# TrackerBase2.net
KiCad netlist of a schematic drawn in EAGLE
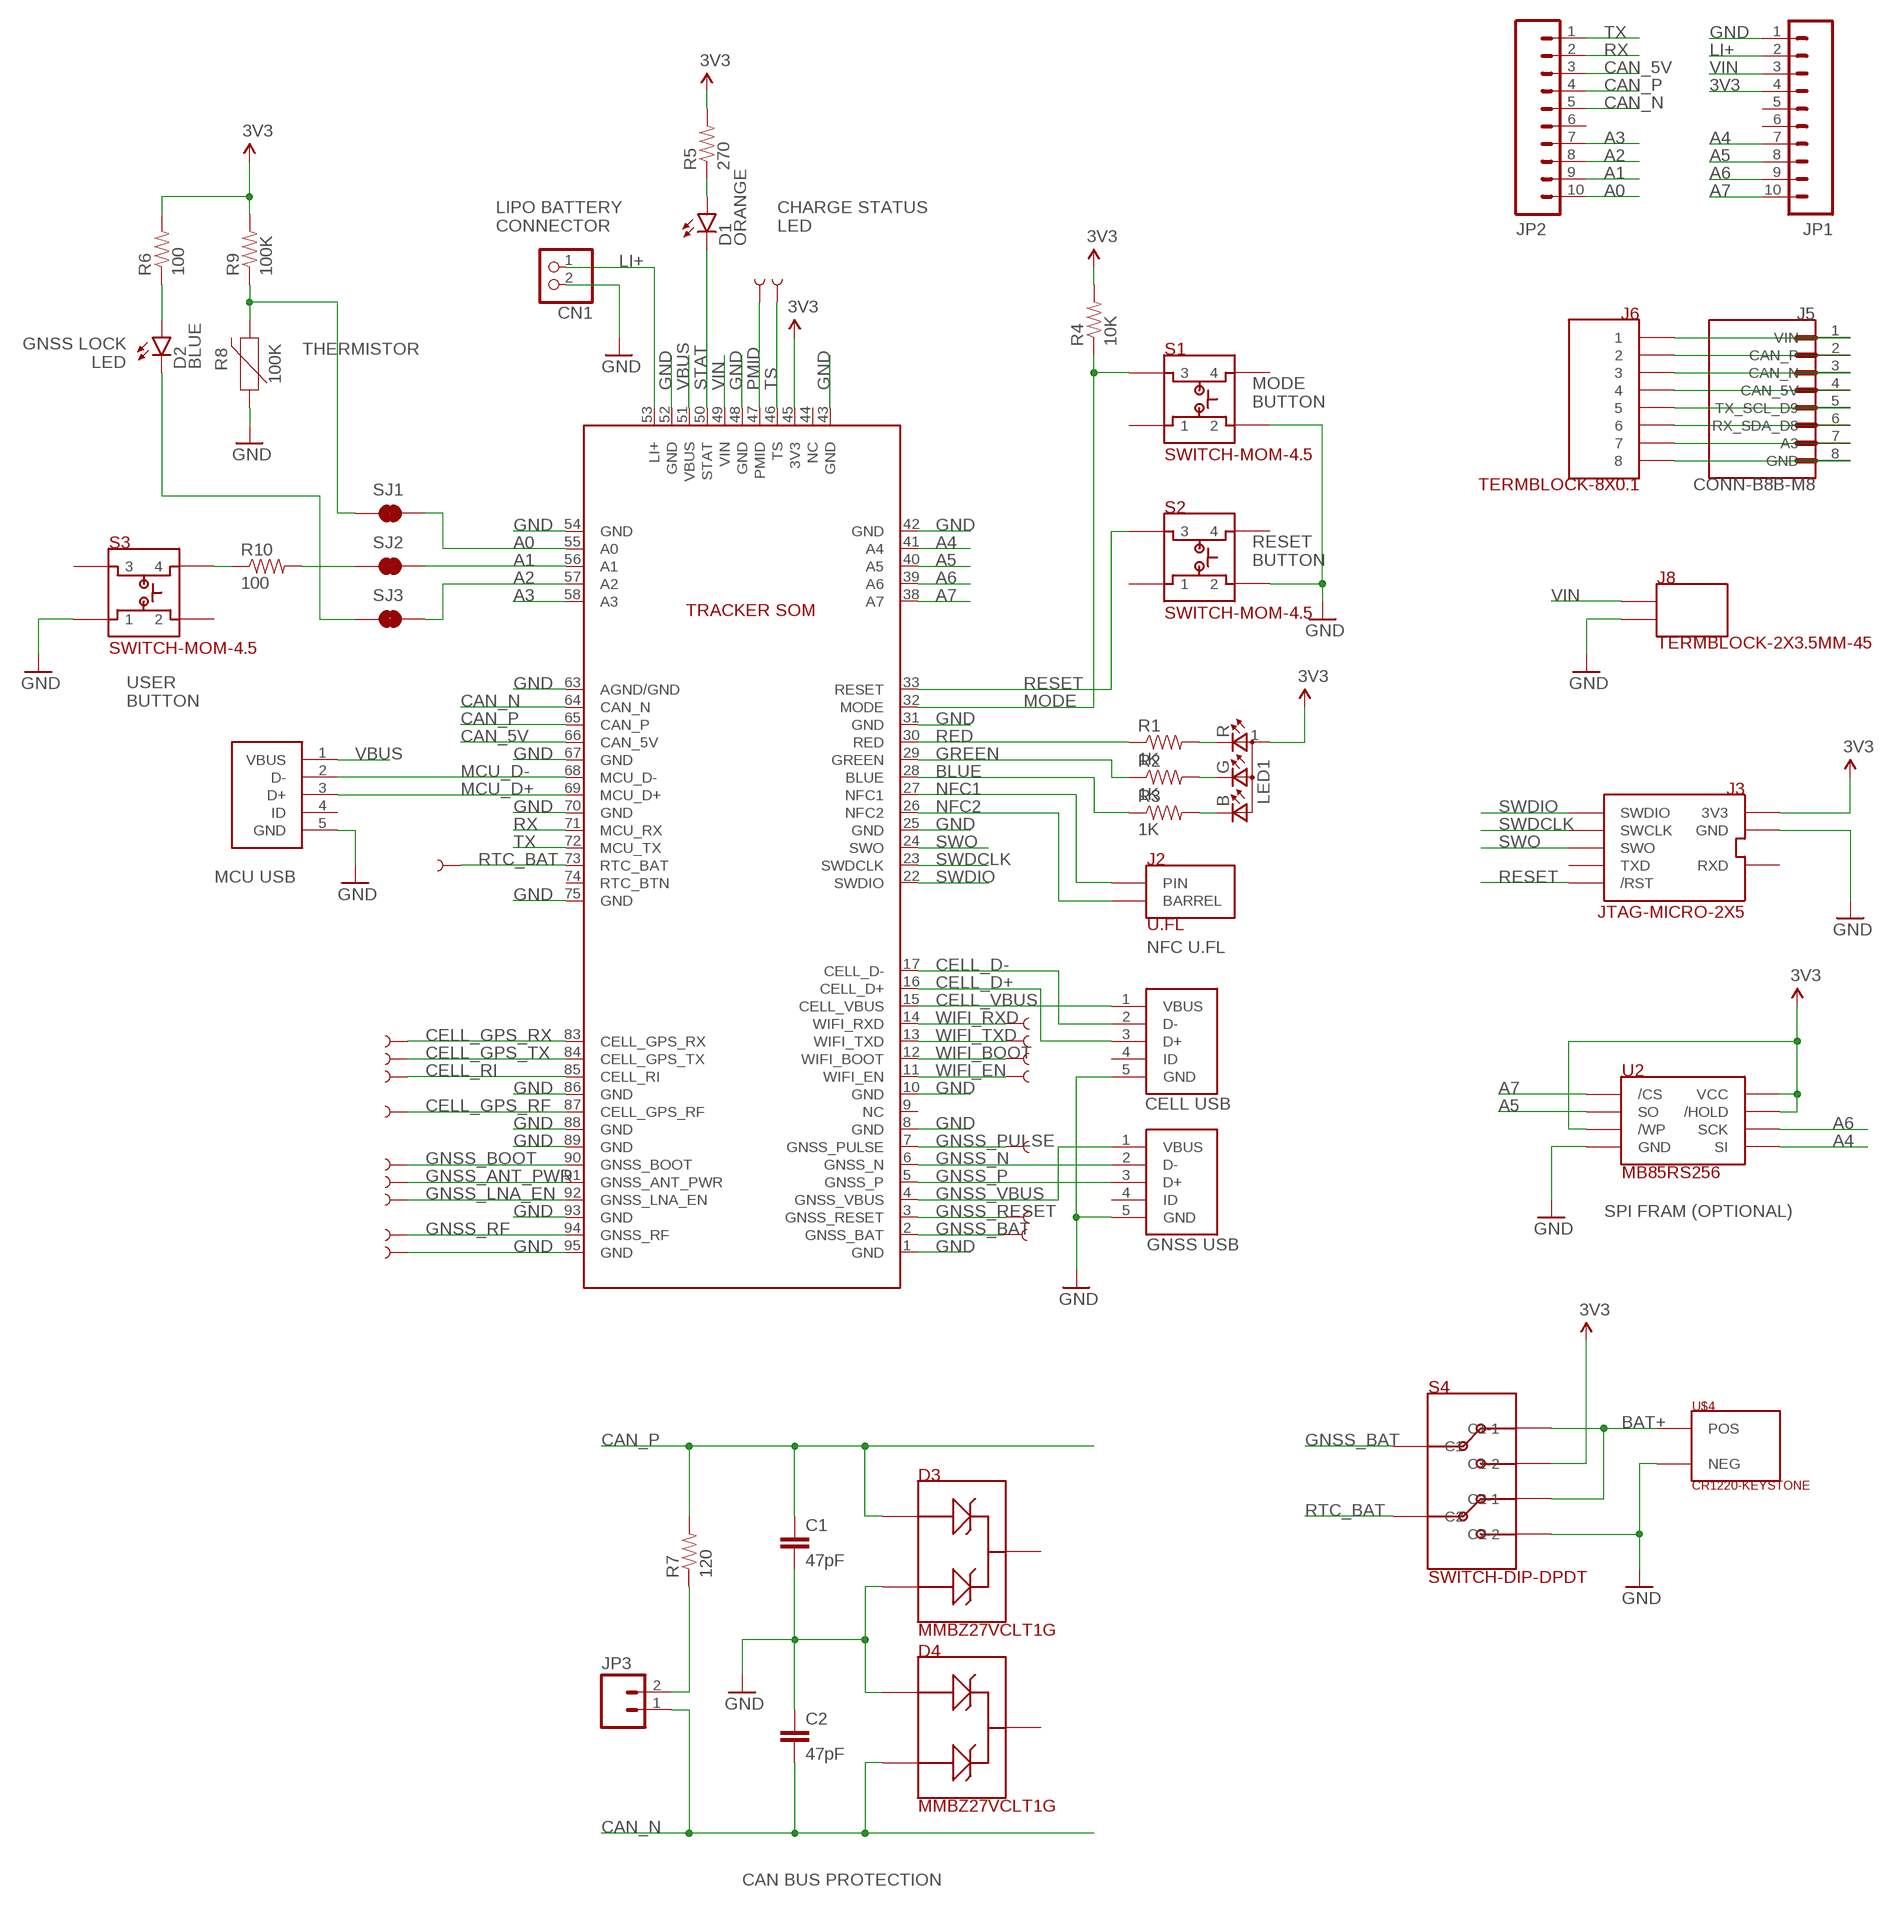
[diagram p0: schematic, sheet 1]

(export (version "E")
  (design (tool "Eeschema 10.0.6"))
  (components
    (comp (ref "C1")
      (value "47pF")
      (footprint "eagle-import:0603-CAP")
      (libsource (lib "eagle-import") (part "CAP-47PF-0603"))
    )
    (comp (ref "C2")
      (value "47pF")
      (footprint "eagle-import:0603-CAP")
      (libsource (lib "eagle-import") (part "CAP-47PF-0603"))
    )
    (comp (ref "CN1")
      (value "JST_2PIN-THM")
      (footprint "eagle-import:JST-PH-2-THM")
      (libsource (lib "eagle-import") (part "JST_2PIN-THM"))
    )
    (comp (ref "D1")
      (value "ORANGE")
      (footprint "eagle-import:LED-0603")
      (libsource (lib "eagle-import") (part "LED-ORANGE0603"))
    )
    (comp (ref "D2")
      (value "BLUE")
      (footprint "eagle-import:LED-0603")
      (libsource (lib "eagle-import") (part "LED-BLUE0603"))
    )
    (comp (ref "D3")
      (value "MMBZ27VCLT1G")
      (footprint "eagle-import:SOT-23-3-ON")
      (libsource (lib "eagle-import") (part "TVS-MMBZ27VCLT1G"))
    )
    (comp (ref "D4")
      (value "MMBZ27VCLT1G")
      (footprint "eagle-import:SOT-23-3-ON")
      (libsource (lib "eagle-import") (part "TVS-MMBZ27VCLT1G"))
    )
    (comp (ref "J1")
      (value "USB-MICRO-B-VERT-PTH")
      (footprint "eagle-import:USB-MICRO-B-VERT-PTH")
      (libsource (lib "eagle-import") (part "USB-MICRO-B-VERT-PTH"))
    )
    (comp (ref "J2")
      (value "U.FL")
      (footprint "eagle-import:CONN-UFL-TE")
      (libsource (lib "eagle-import") (part "CONN-UFL-TE"))
    )
    (comp (ref "J3")
      (value "JTAG-MICRO-2X5")
      (footprint "eagle-import:JTAG-MICRO-2X5")
      (libsource (lib "eagle-import") (part "JTAG-MICRO-2X5"))
    )
    (comp (ref "J4")
      (value "USB-MICRO-B-VERT-PTH")
      (footprint "eagle-import:USB-MICRO-B-VERT-PTH")
      (libsource (lib "eagle-import") (part "USB-MICRO-B-VERT-PTH"))
    )
    (comp (ref "J5")
      (value "CONN-B8B-M8")
      (footprint "eagle-import:JST_B8B-PH-SM4-TB(LF)(SN)")
      (libsource (lib "eagle-import") (part "CONN-B8B-M8"))
    )
    (comp (ref "J6")
      (value "TERMBLOCK-8X0.1")
      (footprint "eagle-import:TERMBLOCK-8X0.1")
      (libsource (lib "eagle-import") (part "TERMBLOCK-8X0.1"))
    )
    (comp (ref "J7")
      (value "USB-MICRO-B-VERT-PTH")
      (footprint "eagle-import:USB-MICRO-B-VERT-PTH")
      (libsource (lib "eagle-import") (part "USB-MICRO-B-VERT-PTH"))
    )
    (comp (ref "J8")
      (value "TERMBLOCK-2X3.5MM-45")
      (footprint "eagle-import:TERMBLOCK-2X3.5MM-45")
      (libsource (lib "eagle-import") (part "TERMBLOCK-2X3.5MM-45"))
    )
    (comp (ref "JP1")
      (value "M10")
      (footprint "eagle-import:1X10")
      (libsource (lib "eagle-import") (part "M10"))
    )
    (comp (ref "JP2")
      (value "M10")
      (footprint "eagle-import:1X10")
      (libsource (lib "eagle-import") (part "M10"))
    )
    (comp (ref "JP3")
      (value "M02PTH")
      (footprint "eagle-import:1X02")
      (libsource (lib "eagle-import") (part "M02PTH"))
    )
    (comp (ref "LED1")
      (value "RGB")
      (footprint "eagle-import:LED-RGB-CREE-SMD")
      (libsource (lib "eagle-import") (part "LED-RGB-CREE-SMD"))
    )
    (comp (ref "R1")
      (value "1K")
      (footprint "eagle-import:0603-RES")
      (libsource (lib "eagle-import") (part "RES-1K-0603"))
    )
    (comp (ref "R2")
      (value "1K")
      (footprint "eagle-import:0603-RES")
      (libsource (lib "eagle-import") (part "RES-1K-0603"))
    )
    (comp (ref "R3")
      (value "1K")
      (footprint "eagle-import:0603-RES")
      (libsource (lib "eagle-import") (part "RES-1K-0603"))
    )
    (comp (ref "R4")
      (value "10K")
      (footprint "eagle-import:0603-RES")
      (libsource (lib "eagle-import") (part "RES-10K-06030603"))
    )
    (comp (ref "R5")
      (value "270")
      (footprint "eagle-import:0603-RES")
      (libsource (lib "eagle-import") (part "RES-270-0603.DEV"))
    )
    (comp (ref "R6")
      (value "100")
      (footprint "eagle-import:0603-RES")
      (libsource (lib "eagle-import") (part "RES-100-0603.DEV"))
    )
    (comp (ref "R7")
      (value "120")
      (footprint "eagle-import:0603-RES")
      (libsource (lib "eagle-import") (part "RES-120-0603"))
    )
    (comp (ref "R8")
      (value "100K")
      (footprint "eagle-import:0603")
      (libsource (lib "eagle-import") (part "NTC-THERMISTOR-0603"))
    )
    (comp (ref "R9")
      (value "100K")
      (footprint "eagle-import:0603-RES")
      (libsource (lib "eagle-import") (part "RES-100K-0603"))
    )
    (comp (ref "R10")
      (value "100")
      (footprint "eagle-import:0603-RES")
      (libsource (lib "eagle-import") (part "RES-100-0603.DEV"))
    )
    (comp (ref "S1")
      (value "SWITCH-MOM-4.5")
      (footprint "eagle-import:SWITCH-MOM-4.5")
      (libsource (lib "eagle-import") (part "SWITCH-MOM-4.5"))
    )
    (comp (ref "S2")
      (value "SWITCH-MOM-4.5")
      (footprint "eagle-import:SWITCH-MOM-4.5")
      (libsource (lib "eagle-import") (part "SWITCH-MOM-4.5"))
    )
    (comp (ref "S3")
      (value "SWITCH-MOM-4.5")
      (footprint "eagle-import:SWITCH-MOM-4.5")
      (libsource (lib "eagle-import") (part "SWITCH-MOM-4.5"))
    )
    (comp (ref "S4")
      (value "SWITCH-DIP-DPDT")
      (footprint "eagle-import:SWITCH-DIP-DPDT")
      (libsource (lib "eagle-import") (part "SWITCH-DIP-DPDT"))
    )
    (comp (ref "SJ1")
      (value "JUMPER-PAD-2-NC_BY_TRACENO_SILK")
      (footprint "eagle-import:PAD-JUMPER-2-NC_BY_TRACE_NO_SILK")
      (libsource (lib "eagle-import") (part "JUMPER-PAD-2-NC_BY_TRACENO_SILK"))
    )
    (comp (ref "SJ2")
      (value "JUMPER-PAD-2-NC_BY_TRACENO_SILK")
      (footprint "eagle-import:PAD-JUMPER-2-NC_BY_TRACE_NO_SILK")
      (libsource (lib "eagle-import") (part "JUMPER-PAD-2-NC_BY_TRACENO_SILK"))
    )
    (comp (ref "SJ3")
      (value "JUMPER-PAD-2-NC_BY_TRACENO_SILK")
      (footprint "eagle-import:PAD-JUMPER-2-NC_BY_TRACE_NO_SILK")
      (libsource (lib "eagle-import") (part "JUMPER-PAD-2-NC_BY_TRACENO_SILK"))
    )
    (comp (ref "TP1")
      (value "TEST-POINTTP_15TH_THRU")
      (footprint "eagle-import:TP_15TH")
      (libsource (lib "eagle-import") (part "TEST-POINTTP_15TH_THRU"))
    )
    (comp (ref "TP2")
      (value "TEST-POINTTP_15TH_THRU")
      (footprint "eagle-import:TP_15TH")
      (libsource (lib "eagle-import") (part "TEST-POINTTP_15TH_THRU"))
    )
    (comp (ref "TP3")
      (value "TEST-POINTTP_15TH_THRU")
      (footprint "eagle-import:TP_15TH")
      (libsource (lib "eagle-import") (part "TEST-POINTTP_15TH_THRU"))
    )
    (comp (ref "TP4")
      (value "TEST-POINTTP_15TH_THRU")
      (footprint "eagle-import:TP_15TH")
      (libsource (lib "eagle-import") (part "TEST-POINTTP_15TH_THRU"))
    )
    (comp (ref "TP5")
      (value "TEST-POINTTP_15TH_THRU")
      (footprint "eagle-import:TP_15TH")
      (libsource (lib "eagle-import") (part "TEST-POINTTP_15TH_THRU"))
    )
    (comp (ref "TP6")
      (value "TEST-POINTTP_15TH_THRU")
      (footprint "eagle-import:TP_15TH")
      (libsource (lib "eagle-import") (part "TEST-POINTTP_15TH_THRU"))
    )
    (comp (ref "TP7")
      (value "TEST-POINTTP_15TH_THRU")
      (footprint "eagle-import:TP_15TH")
      (libsource (lib "eagle-import") (part "TEST-POINTTP_15TH_THRU"))
    )
    (comp (ref "TP8")
      (value "TEST-POINTTP_15TH_THRU")
      (footprint "eagle-import:TP_15TH")
      (libsource (lib "eagle-import") (part "TEST-POINTTP_15TH_THRU"))
    )
    (comp (ref "TP9")
      (value "TEST-POINTTP_15TH_THRU")
      (footprint "eagle-import:TP_15TH")
      (libsource (lib "eagle-import") (part "TEST-POINTTP_15TH_THRU"))
    )
    (comp (ref "TP10")
      (value "TEST-POINTTP_15TH_THRU")
      (footprint "eagle-import:TP_15TH")
      (libsource (lib "eagle-import") (part "TEST-POINTTP_15TH_THRU"))
    )
    (comp (ref "TP11")
      (value "TEST-POINTTP_15TH_THRU")
      (footprint "eagle-import:TP_15TH")
      (libsource (lib "eagle-import") (part "TEST-POINTTP_15TH_THRU"))
    )
    (comp (ref "TP12")
      (value "TEST-POINTTP_15TH_THRU")
      (footprint "eagle-import:TP_15TH")
      (libsource (lib "eagle-import") (part "TEST-POINTTP_15TH_THRU"))
    )
    (comp (ref "TP13")
      (value "TEST-POINTTP_15TH_THRU")
      (footprint "eagle-import:TP_15TH")
      (libsource (lib "eagle-import") (part "TEST-POINTTP_15TH_THRU"))
    )
    (comp (ref "TP14")
      (value "TEST-POINTTP_15TH_THRU")
      (footprint "eagle-import:TP_15TH")
      (libsource (lib "eagle-import") (part "TEST-POINTTP_15TH_THRU"))
    )
    (comp (ref "TP15")
      (value "TEST-POINTTP_15TH_THRU")
      (footprint "eagle-import:TP_15TH")
      (libsource (lib "eagle-import") (part "TEST-POINTTP_15TH_THRU"))
    )
    (comp (ref "TP16")
      (value "TEST-POINTTP_15TH_THRU")
      (footprint "eagle-import:TP_15TH")
      (libsource (lib "eagle-import") (part "TEST-POINTTP_15TH_THRU"))
    )
    (comp (ref "TP17")
      (value "TEST-POINTTP_15TH_THRU")
      (footprint "eagle-import:TP_15TH")
      (libsource (lib "eagle-import") (part "TEST-POINTTP_15TH_THRU"))
    )
    (comp (ref "TP18")
      (value "TEST-POINTTP_15TH_THRU")
      (footprint "eagle-import:TP_15TH")
      (libsource (lib "eagle-import") (part "TEST-POINTTP_15TH_THRU"))
    )
    (comp (ref "TP19")
      (value "TEST-POINTTP_15TH_THRU")
      (footprint "eagle-import:TP_15TH")
      (libsource (lib "eagle-import") (part "TEST-POINTTP_15TH_THRU"))
    )
    (comp (ref "U$4")
      (value "CR1220-KEYSTONE")
      (footprint "eagle-import:CR1220-KEYSTONE")
      (libsource (lib "eagle-import") (part "CR1220-KEYSTONE"))
    )
    (comp (ref "U1")
      (value "TRACKER-SOM-SKIP-NC")
      (footprint "eagle-import:TRACKER-SOM-SKIP-NC")
      (libsource (lib "eagle-import") (part "TRACKER-SOM-SKIP-NC"))
    )
    (comp (ref "U2")
      (value "MB85RS256")
      (footprint "eagle-import:8-SOIC-MAXIM")
      (libsource (lib "eagle-import") (part "MB85RS256-FRAM"))
    )
  )
  (nets
    (net (code "1") (name "/A0") (class "Default")
      (node (ref "JP2") (pin "10") (pinfunction "10_10") (pintype "passive"))
      (node (ref "SJ1") (pin "2") (pinfunction "2_2") (pintype "passive"))
      (node (ref "U1") (pin "55") (pinfunction "A0_55") (pintype "bidirectional"))
    )
    (net (code "2") (name "/A1") (class "Default")
      (node (ref "JP2") (pin "9") (pinfunction "9_9") (pintype "passive"))
      (node (ref "SJ2") (pin "2") (pinfunction "2_2") (pintype "passive"))
      (node (ref "U1") (pin "56") (pinfunction "A1_56") (pintype "bidirectional"))
    )
    (net (code "3") (name "/A2") (class "Default")
      (node (ref "JP2") (pin "8") (pinfunction "8_8") (pintype "passive"))
      (node (ref "SJ3") (pin "2") (pinfunction "2_2") (pintype "passive"))
      (node (ref "U1") (pin "57") (pinfunction "A2_57") (pintype "bidirectional"))
    )
    (net (code "4") (name "/A3") (class "Default")
      (node (ref "J5") (pin "7") (pinfunction "A3_7") (pintype "passive"))
      (node (ref "J6") (pin "P$7") (pinfunction "7_P$7") (pintype "passive"))
      (node (ref "JP2") (pin "7") (pinfunction "7_7") (pintype "passive"))
      (node (ref "U1") (pin "58") (pinfunction "A3_58") (pintype "bidirectional"))
    )
    (net (code "5") (name "/A4") (class "Default")
      (node (ref "JP1") (pin "7") (pinfunction "7_7") (pintype "passive"))
      (node (ref "U1") (pin "41") (pinfunction "A4_41") (pintype "bidirectional"))
      (node (ref "U2") (pin "5") (pinfunction "SI_5") (pintype "input"))
    )
    (net (code "6") (name "/A5") (class "Default")
      (node (ref "JP1") (pin "8") (pinfunction "8_8") (pintype "passive"))
      (node (ref "U1") (pin "40") (pinfunction "A5_40") (pintype "bidirectional"))
      (node (ref "U2") (pin "2") (pinfunction "SO_2") (pintype "output"))
    )
    (net (code "7") (name "/A6") (class "Default")
      (node (ref "JP1") (pin "9") (pinfunction "9_9") (pintype "passive"))
      (node (ref "U1") (pin "39") (pinfunction "A6_39") (pintype "bidirectional"))
      (node (ref "U2") (pin "6") (pinfunction "SCK_6") (pintype "input"))
    )
    (net (code "8") (name "/A7") (class "Default")
      (node (ref "JP1") (pin "10") (pinfunction "10_10") (pintype "passive"))
      (node (ref "U1") (pin "38") (pinfunction "A7_38") (pintype "bidirectional"))
      (node (ref "U2") (pin "1") (pinfunction "/CS_1") (pintype "input"))
    )
    (net (code "9") (name "/BAT+") (class "Default")
      (node (ref "S4") (pin "C1-1") (pinfunction "C1-1_C1-1") (pintype "passive"))
      (node (ref "S4") (pin "C2-1") (pinfunction "C2-1_C2-1") (pintype "passive"))
      (node (ref "U$4") (pin "POS") (pinfunction "POS_POS") (pintype "passive"))
    )
    (net (code "10") (name "/BLUE") (class "Default")
      (node (ref "R3") (pin "1") (pinfunction "1_1") (pintype "passive"))
      (node (ref "U1") (pin "28") (pinfunction "BLUE_28") (pintype "bidirectional"))
    )
    (net (code "11") (name "/CAN_5V") (class "Default")
      (node (ref "J5") (pin "4") (pinfunction "CAN_5V_4") (pintype "passive"))
      (node (ref "J6") (pin "P$4") (pinfunction "4_P$4") (pintype "passive"))
      (node (ref "JP2") (pin "3") (pinfunction "3_3") (pintype "passive"))
      (node (ref "U1") (pin "66") (pinfunction "CAN_5V_66") (pintype "bidirectional"))
    )
    (net (code "12") (name "/CAN_N") (class "Default")
      (node (ref "C2") (pin "2") (pinfunction "2_2") (pintype "passive"))
      (node (ref "D4") (pin "2") (pinfunction "2_2") (pintype "bidirectional"))
      (node (ref "J5") (pin "3") (pinfunction "CAN_N_3") (pintype "passive"))
      (node (ref "J6") (pin "P$3") (pinfunction "3_P$3") (pintype "passive"))
      (node (ref "JP2") (pin "5") (pinfunction "5_5") (pintype "passive"))
      (node (ref "JP3") (pin "1") (pinfunction "1_1") (pintype "passive"))
      (node (ref "U1") (pin "64") (pinfunction "CAN_N_64") (pintype "bidirectional"))
    )
    (net (code "13") (name "/CAN_P") (class "Default")
      (node (ref "C1") (pin "1") (pinfunction "1_1") (pintype "passive"))
      (node (ref "D3") (pin "1") (pinfunction "1_1") (pintype "bidirectional"))
      (node (ref "J5") (pin "2") (pinfunction "CAN_P_2") (pintype "passive"))
      (node (ref "J6") (pin "P$2") (pinfunction "2_P$2") (pintype "passive"))
      (node (ref "JP2") (pin "4") (pinfunction "4_4") (pintype "passive"))
      (node (ref "R7") (pin "2") (pinfunction "2_2") (pintype "passive"))
      (node (ref "U1") (pin "65") (pinfunction "CAN_P_65") (pintype "bidirectional"))
    )
    (net (code "14") (name "/CELL_D+") (class "Default")
      (node (ref "J1") (pin "3") (pinfunction "D+_3") (pintype "passive"))
      (node (ref "U1") (pin "16") (pinfunction "CELL_D+_16") (pintype "bidirectional"))
    )
    (net (code "15") (name "/CELL_D-") (class "Default")
      (node (ref "J1") (pin "2") (pinfunction "D-_2") (pintype "passive"))
      (node (ref "U1") (pin "17") (pinfunction "CELL_D-_17") (pintype "bidirectional"))
    )
    (net (code "16") (name "/CELL_GPS_RF") (class "Default")
      (node (ref "TP14") (pin "P$1") (pinfunction "1_P$1") (pintype "bidirectional"))
      (node (ref "U1") (pin "87") (pinfunction "CELL_GPS_RF_87") (pintype "bidirectional"))
    )
    (net (code "17") (name "/CELL_GPS_RX") (class "Default")
      (node (ref "TP7") (pin "P$1") (pinfunction "1_P$1") (pintype "bidirectional"))
      (node (ref "U1") (pin "83") (pinfunction "CELL_GPS_RX_83") (pintype "bidirectional"))
    )
    (net (code "18") (name "/CELL_GPS_TX") (class "Default")
      (node (ref "TP8") (pin "P$1") (pinfunction "1_P$1") (pintype "bidirectional"))
      (node (ref "U1") (pin "84") (pinfunction "CELL_GPS_TX_84") (pintype "bidirectional"))
    )
    (net (code "19") (name "/CELL_RI") (class "Default")
      (node (ref "TP9") (pin "P$1") (pinfunction "1_P$1") (pintype "bidirectional"))
      (node (ref "U1") (pin "85") (pinfunction "CELL_RI_85") (pintype "bidirectional"))
    )
    (net (code "20") (name "/CELL_VBUS") (class "Default")
      (node (ref "J1") (pin "1") (pinfunction "VBUS_1") (pintype "passive"))
      (node (ref "U1") (pin "15") (pinfunction "CELL_VBUS_15") (pintype "bidirectional"))
    )
    (net (code "21") (name "/GNSS_ANT_PWR") (class "Default")
      (node (ref "TP11") (pin "P$1") (pinfunction "1_P$1") (pintype "bidirectional"))
      (node (ref "U1") (pin "91") (pinfunction "GNSS_ANT_PWR_91") (pintype "bidirectional"))
    )
    (net (code "22") (name "/GNSS_BAT") (class "Default")
      (node (ref "S4") (pin "C1") (pinfunction "C1_C1") (pintype "passive"))
      (node (ref "TP17") (pin "P$1") (pinfunction "1_P$1") (pintype "bidirectional"))
      (node (ref "U1") (pin "2") (pinfunction "GNSS_BAT_2") (pintype "bidirectional"))
    )
    (net (code "23") (name "/GNSS_BOOT") (class "Default")
      (node (ref "TP10") (pin "P$1") (pinfunction "1_P$1") (pintype "bidirectional"))
      (node (ref "U1") (pin "90") (pinfunction "GNSS_BOOT_90") (pintype "bidirectional"))
    )
    (net (code "24") (name "/GNSS_LNA_EN") (class "Default")
      (node (ref "TP12") (pin "P$1") (pinfunction "1_P$1") (pintype "bidirectional"))
      (node (ref "U1") (pin "92") (pinfunction "GNSS_LNA_EN_92") (pintype "bidirectional"))
    )
    (net (code "25") (name "/GNSS_N") (class "Default")
      (node (ref "J4") (pin "2") (pinfunction "D-_2") (pintype "passive"))
      (node (ref "U1") (pin "6") (pinfunction "GNSS_N_6") (pintype "bidirectional"))
    )
    (net (code "26") (name "/GNSS_P") (class "Default")
      (node (ref "J4") (pin "3") (pinfunction "D+_3") (pintype "passive"))
      (node (ref "U1") (pin "5") (pinfunction "GNSS_P_5") (pintype "bidirectional"))
    )
    (net (code "27") (name "/GNSS_PULSE") (class "Default")
      (node (ref "TP5") (pin "P$1") (pinfunction "1_P$1") (pintype "bidirectional"))
      (node (ref "U1") (pin "7") (pinfunction "GNSS_PULSE_7") (pintype "bidirectional"))
    )
    (net (code "28") (name "/GNSS_RESET") (class "Default")
      (node (ref "TP6") (pin "P$1") (pinfunction "1_P$1") (pintype "bidirectional"))
      (node (ref "U1") (pin "3") (pinfunction "GNSS_RESET_3") (pintype "bidirectional"))
    )
    (net (code "29") (name "/GNSS_RF") (class "Default")
      (node (ref "TP13") (pin "P$1") (pinfunction "1_P$1") (pintype "bidirectional"))
      (node (ref "U1") (pin "94") (pinfunction "GNSS_RF_94") (pintype "bidirectional"))
    )
    (net (code "30") (name "/GNSS_VBUS") (class "Default")
      (node (ref "J4") (pin "1") (pinfunction "VBUS_1") (pintype "passive"))
      (node (ref "U1") (pin "4") (pinfunction "GNSS_VBUS_4") (pintype "bidirectional"))
    )
    (net (code "31") (name "/GREEN") (class "Default")
      (node (ref "R2") (pin "1") (pinfunction "1_1") (pintype "passive"))
      (node (ref "U1") (pin "29") (pinfunction "GREEN_29") (pintype "bidirectional"))
    )
    (net (code "32") (name "/LI+") (class "Default")
      (node (ref "CN1") (pin "1") (pinfunction "2_1") (pintype "passive"))
      (node (ref "JP1") (pin "2") (pinfunction "2_2") (pintype "passive"))
      (node (ref "U1") (pin "53") (pinfunction "LI+_53") (pintype "bidirectional"))
    )
    (net (code "33") (name "/MCU_D+") (class "Default")
      (node (ref "J7") (pin "3") (pinfunction "D+_3") (pintype "passive"))
      (node (ref "U1") (pin "69") (pinfunction "MCU_D+_69") (pintype "bidirectional"))
    )
    (net (code "34") (name "/MCU_D-") (class "Default")
      (node (ref "J7") (pin "2") (pinfunction "D-_2") (pintype "passive"))
      (node (ref "U1") (pin "68") (pinfunction "MCU_D-_68") (pintype "bidirectional"))
    )
    (net (code "35") (name "/MODE") (class "Default")
      (node (ref "R4") (pin "1") (pinfunction "1_1") (pintype "passive"))
      (node (ref "S1") (pin "3") (pinfunction "3_3") (pintype "passive"))
      (node (ref "U1") (pin "32") (pinfunction "MODE_32") (pintype "bidirectional"))
    )
    (net (code "36") (name "/NFC1") (class "Default")
      (node (ref "J2") (pin "PIN") (pinfunction "PIN_PIN") (pintype "passive"))
      (node (ref "U1") (pin "27") (pinfunction "NFC1_27") (pintype "bidirectional"))
    )
    (net (code "37") (name "/NFC2") (class "Default")
      (node (ref "J2") (pin "BL") (pinfunction "BARREL_BL") (pintype "passive"))
      (node (ref "J2") (pin "BR") (pinfunction "BARREL_BR") (pintype "passive"))
      (node (ref "U1") (pin "26") (pinfunction "NFC2_26") (pintype "bidirectional"))
    )
    (net (code "38") (name "/PMID") (class "Default")
      (node (ref "TP15") (pin "P$1") (pinfunction "1_P$1") (pintype "bidirectional"))
      (node (ref "U1") (pin "47") (pinfunction "PMID_47") (pintype "bidirectional"))
    )
    (net (code "39") (name "/RED") (class "Default")
      (node (ref "R1") (pin "1") (pinfunction "1_1") (pintype "passive"))
      (node (ref "U1") (pin "30") (pinfunction "RED_30") (pintype "bidirectional"))
    )
    (net (code "40") (name "/RESET") (class "Default")
      (node (ref "J3") (pin "10") (pinfunction "/RST_10") (pintype "passive"))
      (node (ref "S2") (pin "3") (pinfunction "3_3") (pintype "passive"))
      (node (ref "U1") (pin "33") (pinfunction "RESET_33") (pintype "bidirectional"))
    )
    (net (code "41") (name "/RTC_BAT") (class "Default")
      (node (ref "S4") (pin "C2") (pinfunction "C2_C2") (pintype "passive"))
      (node (ref "TP18") (pin "P$1") (pinfunction "1_P$1") (pintype "bidirectional"))
      (node (ref "U1") (pin "73") (pinfunction "RTC_BAT_73") (pintype "bidirectional"))
    )
    (net (code "42") (name "/RX") (class "Default")
      (node (ref "J5") (pin "6") (pinfunction "RX_SDA_D8_6") (pintype "passive"))
      (node (ref "J6") (pin "P$6") (pinfunction "6_P$6") (pintype "passive"))
      (node (ref "JP2") (pin "2") (pinfunction "2_2") (pintype "passive"))
      (node (ref "U1") (pin "71") (pinfunction "MCU_RX_71") (pintype "bidirectional"))
    )
    (net (code "43") (name "/STAT") (class "Default")
      (node (ref "D1") (pin "C") (pinfunction "C_C") (pintype "passive"))
      (node (ref "U1") (pin "50") (pinfunction "STAT_50") (pintype "bidirectional"))
    )
    (net (code "44") (name "/SWDCLK") (class "Default")
      (node (ref "J3") (pin "4") (pinfunction "SWCLK_4") (pintype "passive"))
      (node (ref "U1") (pin "23") (pinfunction "SWDCLK_23") (pintype "bidirectional"))
    )
    (net (code "45") (name "/SWDIO") (class "Default")
      (node (ref "J3") (pin "2") (pinfunction "SWDIO_2") (pintype "passive"))
      (node (ref "U1") (pin "22") (pinfunction "SWDIO_22") (pintype "bidirectional"))
    )
    (net (code "46") (name "/SWO") (class "Default")
      (node (ref "J3") (pin "6") (pinfunction "SWO_6") (pintype "passive"))
      (node (ref "U1") (pin "24") (pinfunction "SWO_24") (pintype "bidirectional"))
    )
    (net (code "47") (name "/TS") (class "Default")
      (node (ref "TP16") (pin "P$1") (pinfunction "1_P$1") (pintype "bidirectional"))
      (node (ref "U1") (pin "46") (pinfunction "TS_46") (pintype "bidirectional"))
    )
    (net (code "48") (name "/TX") (class "Default")
      (node (ref "J5") (pin "5") (pinfunction "TX_SCL_D9_5") (pintype "passive"))
      (node (ref "J6") (pin "P$5") (pinfunction "5_P$5") (pintype "passive"))
      (node (ref "JP2") (pin "1") (pinfunction "1_1") (pintype "passive"))
      (node (ref "U1") (pin "72") (pinfunction "MCU_TX_72") (pintype "bidirectional"))
    )
    (net (code "49") (name "/VBUS") (class "Default")
      (node (ref "J7") (pin "1") (pinfunction "VBUS_1") (pintype "passive"))
      (node (ref "U1") (pin "51") (pinfunction "VBUS_51") (pintype "bidirectional"))
    )
    (net (code "50") (name "/VIN") (class "Default")
      (node (ref "J5") (pin "1") (pinfunction "VIN_1") (pintype "passive"))
      (node (ref "J6") (pin "P$1") (pinfunction "1_P$1") (pintype "passive"))
      (node (ref "J8") (pin "1") (pinfunction "1_1") (pintype "passive"))
      (node (ref "JP1") (pin "3") (pinfunction "3_3") (pintype "passive"))
      (node (ref "U1") (pin "49") (pinfunction "VIN_49") (pintype "bidirectional"))
    )
    (net (code "51") (name "/WIFI_BOOT") (class "Default")
      (node (ref "TP3") (pin "P$1") (pinfunction "1_P$1") (pintype "bidirectional"))
      (node (ref "U1") (pin "12") (pinfunction "WIFI_BOOT_12") (pintype "bidirectional"))
    )
    (net (code "52") (name "/WIFI_EN") (class "Default")
      (node (ref "TP4") (pin "P$1") (pinfunction "1_P$1") (pintype "bidirectional"))
      (node (ref "U1") (pin "11") (pinfunction "WIFI_EN_11") (pintype "bidirectional"))
    )
    (net (code "53") (name "/WIFI_RXD") (class "Default")
      (node (ref "TP1") (pin "P$1") (pinfunction "1_P$1") (pintype "bidirectional"))
      (node (ref "U1") (pin "14") (pinfunction "WIFI_RXD_14") (pintype "bidirectional"))
    )
    (net (code "54") (name "/WIFI_TXD") (class "Default")
      (node (ref "TP2") (pin "P$1") (pinfunction "1_P$1") (pintype "bidirectional"))
      (node (ref "U1") (pin "13") (pinfunction "WIFI_TXD_13") (pintype "bidirectional"))
    )
    (net (code "55") (name "3V3") (class "Default")
      (node (ref "J3") (pin "1") (pinfunction "3V3_1") (pintype "passive"))
      (node (ref "JP1") (pin "4") (pinfunction "4_4") (pintype "passive"))
      (node (ref "LED1") (pin "1") (pinfunction "A_1") (pintype "passive"))
      (node (ref "R4") (pin "2") (pinfunction "2_2") (pintype "passive"))
      (node (ref "R5") (pin "2") (pinfunction "2_2") (pintype "passive"))
      (node (ref "R6") (pin "2") (pinfunction "2_2") (pintype "passive"))
      (node (ref "R9") (pin "2") (pinfunction "2_2") (pintype "passive"))
      (node (ref "S4") (pin "C1-2") (pinfunction "C1-2_C1-2") (pintype "passive"))
      (node (ref "U1") (pin "45") (pinfunction "3V3_45") (pintype "bidirectional"))
      (node (ref "U2") (pin "3") (pinfunction "/WP_3") (pintype "input"))
      (node (ref "U2") (pin "7") (pinfunction "/HOLD_7") (pintype "input"))
      (node (ref "U2") (pin "8") (pinfunction "VCC_8") (pintype "power_in"))
    )
    (net (code "56") (name "GND") (class "Default")
      (node (ref "C1") (pin "2") (pinfunction "2_2") (pintype "passive"))
      (node (ref "C2") (pin "1") (pinfunction "1_1") (pintype "passive"))
      (node (ref "CN1") (pin "2") (pinfunction "1_2") (pintype "passive"))
      (node (ref "D3") (pin "2") (pinfunction "2_2") (pintype "bidirectional"))
      (node (ref "D4") (pin "1") (pinfunction "1_1") (pintype "bidirectional"))
      (node (ref "J1") (pin "5") (pinfunction "GND_5") (pintype "passive"))
      (node (ref "J3") (pin "3") (pinfunction "GND_3") (pintype "passive"))
      (node (ref "J3") (pin "5") (pinfunction "GND_5") (pintype "passive"))
      (node (ref "J3") (pin "9") (pinfunction "GND_9") (pintype "passive"))
      (node (ref "J4") (pin "5") (pinfunction "GND_5") (pintype "passive"))
      (node (ref "J5") (pin "8") (pinfunction "GND_8") (pintype "passive"))
      (node (ref "J6") (pin "P$8") (pinfunction "8_P$8") (pintype "passive"))
      (node (ref "J7") (pin "5") (pinfunction "GND_5") (pintype "passive"))
      (node (ref "J8") (pin "2") (pinfunction "2_2") (pintype "passive"))
      (node (ref "JP1") (pin "1") (pinfunction "1_1") (pintype "passive"))
      (node (ref "R8") (pin "1") (pinfunction "1_1") (pintype "bidirectional"))
      (node (ref "S1") (pin "2") (pinfunction "2_2") (pintype "passive"))
      (node (ref "S2") (pin "2") (pinfunction "2_2") (pintype "passive"))
      (node (ref "S3") (pin "1") (pinfunction "1_1") (pintype "passive"))
      (node (ref "S4") (pin "C2-2") (pinfunction "C2-2_C2-2") (pintype "passive"))
      (node (ref "TP19") (pin "P$1") (pinfunction "1_P$1") (pintype "bidirectional"))
      (node (ref "U$4") (pin "NEG") (pinfunction "NEG_NEG") (pintype "passive"))
      (node (ref "U1") (pin "1") (pinfunction "GND_1") (pintype "bidirectional"))
      (node (ref "U1") (pin "10") (pinfunction "GND_10") (pintype "bidirectional"))
      (node (ref "U1") (pin "25") (pinfunction "GND_25") (pintype "bidirectional"))
      (node (ref "U1") (pin "31") (pinfunction "GND_31") (pintype "bidirectional"))
      (node (ref "U1") (pin "42") (pinfunction "GND_42") (pintype "bidirectional"))
      (node (ref "U1") (pin "43") (pinfunction "GND_43") (pintype "bidirectional"))
      (node (ref "U1") (pin "48") (pinfunction "GND_48") (pintype "bidirectional"))
      (node (ref "U1") (pin "52") (pinfunction "GND_52") (pintype "bidirectional"))
      (node (ref "U1") (pin "54") (pinfunction "GND_54") (pintype "bidirectional"))
      (node (ref "U1") (pin "63") (pinfunction "AGND/GND_63") (pintype "bidirectional"))
      (node (ref "U1") (pin "67") (pinfunction "GND_67") (pintype "bidirectional"))
      (node (ref "U1") (pin "70") (pinfunction "GND_70") (pintype "bidirectional"))
      (node (ref "U1") (pin "75") (pinfunction "GND_75") (pintype "bidirectional"))
      (node (ref "U1") (pin "8") (pinfunction "GND_8") (pintype "bidirectional"))
      (node (ref "U1") (pin "86") (pinfunction "GND_86") (pintype "bidirectional"))
      (node (ref "U1") (pin "88") (pinfunction "GND_88") (pintype "bidirectional"))
      (node (ref "U1") (pin "89") (pinfunction "GND_89") (pintype "bidirectional"))
      (node (ref "U1") (pin "93") (pinfunction "GND_93") (pintype "bidirectional"))
      (node (ref "U1") (pin "95") (pinfunction "GND_95") (pintype "bidirectional"))
      (node (ref "U2") (pin "4") (pinfunction "GND_4") (pintype "passive"))
    )
    (net (code "57") (name "Net-(D1-PadA)") (class "Default")
      (node (ref "D1") (pin "A") (pinfunction "A_A") (pintype "passive"))
      (node (ref "R5") (pin "1") (pinfunction "1_1") (pintype "passive"))
    )
    (net (code "58") (name "Net-(D2-PadA)") (class "Default")
      (node (ref "D2") (pin "A") (pinfunction "A_A") (pintype "passive"))
      (node (ref "R6") (pin "1") (pinfunction "1_1") (pintype "passive"))
    )
    (net (code "59") (name "Net-(D2-PadC)") (class "Default")
      (node (ref "D2") (pin "C") (pinfunction "C_C") (pintype "passive"))
      (node (ref "SJ3") (pin "1") (pinfunction "1_1") (pintype "passive"))
    )
    (net (code "60") (name "Net-(JP3-Pad2)") (class "Default")
      (node (ref "JP3") (pin "2") (pinfunction "2_2") (pintype "passive"))
      (node (ref "R7") (pin "1") (pinfunction "1_1") (pintype "passive"))
    )
    (net (code "61") (name "Net-(LED1-B)") (class "Default")
      (node (ref "LED1") (pin "2") (pinfunction "B_2") (pintype "passive"))
      (node (ref "R3") (pin "2") (pinfunction "2_2") (pintype "passive"))
    )
    (net (code "62") (name "Net-(LED1-G)") (class "Default")
      (node (ref "LED1") (pin "3") (pinfunction "G_3") (pintype "passive"))
      (node (ref "R2") (pin "2") (pinfunction "2_2") (pintype "passive"))
    )
    (net (code "63") (name "Net-(LED1-R)") (class "Default")
      (node (ref "LED1") (pin "4") (pinfunction "R_4") (pintype "passive"))
      (node (ref "R1") (pin "2") (pinfunction "2_2") (pintype "passive"))
    )
    (net (code "64") (name "Net-(R8-Pad2)") (class "Default")
      (node (ref "R8") (pin "2") (pinfunction "2_2") (pintype "bidirectional"))
      (node (ref "R9") (pin "1") (pinfunction "1_1") (pintype "passive"))
      (node (ref "SJ1") (pin "1") (pinfunction "1_1") (pintype "passive"))
    )
    (net (code "65") (name "Net-(R10-Pad1)") (class "Default")
      (node (ref "R10") (pin "1") (pinfunction "1_1") (pintype "passive"))
      (node (ref "S3") (pin "4") (pinfunction "4_4") (pintype "passive"))
    )
    (net (code "66") (name "Net-(R10-Pad2)") (class "Default")
      (node (ref "R10") (pin "2") (pinfunction "2_2") (pintype "passive"))
      (node (ref "SJ2") (pin "1") (pinfunction "1_1") (pintype "passive"))
    )
    (net (code "67") (name "unconnected-(D3-Pad3)") (class "Default")
      (node (ref "D3") (pin "3") (pinfunction "3_3") (pintype "bidirectional"))
    )
    (net (code "68") (name "unconnected-(D4-Pad3)") (class "Default")
      (node (ref "D4") (pin "3") (pinfunction "3_3") (pintype "bidirectional"))
    )
    (net (code "69") (name "unconnected-(J1-ID-Pad4)") (class "Default")
      (node (ref "J1") (pin "4") (pinfunction "ID_4") (pintype "passive"))
    )
    (net (code "70") (name "unconnected-(J3-RXD-Pad7)") (class "Default")
      (node (ref "J3") (pin "7") (pinfunction "RXD_7") (pintype "passive"))
    )
    (net (code "71") (name "unconnected-(J3-TXD-Pad8)") (class "Default")
      (node (ref "J3") (pin "8") (pinfunction "TXD_8") (pintype "passive"))
    )
    (net (code "72") (name "unconnected-(J4-ID-Pad4)") (class "Default")
      (node (ref "J4") (pin "4") (pinfunction "ID_4") (pintype "passive"))
    )
    (net (code "73") (name "unconnected-(J7-ID-Pad4)") (class "Default")
      (node (ref "J7") (pin "4") (pinfunction "ID_4") (pintype "passive"))
    )
    (net (code "74") (name "unconnected-(JP1-Pad5)") (class "Default")
      (node (ref "JP1") (pin "5") (pinfunction "5_5") (pintype "passive"))
    )
    (net (code "75") (name "unconnected-(JP1-Pad6)") (class "Default")
      (node (ref "JP1") (pin "6") (pinfunction "6_6") (pintype "passive"))
    )
    (net (code "76") (name "unconnected-(JP2-Pad6)") (class "Default")
      (node (ref "JP2") (pin "6") (pinfunction "6_6") (pintype "passive"))
    )
    (net (code "77") (name "unconnected-(S1-Pad1)") (class "Default")
      (node (ref "S1") (pin "1") (pinfunction "1_1") (pintype "passive"))
    )
    (net (code "78") (name "unconnected-(S1-Pad4)") (class "Default")
      (node (ref "S1") (pin "4") (pinfunction "4_4") (pintype "passive"))
    )
    (net (code "79") (name "unconnected-(S2-Pad1)") (class "Default")
      (node (ref "S2") (pin "1") (pinfunction "1_1") (pintype "passive"))
    )
    (net (code "80") (name "unconnected-(S2-Pad4)") (class "Default")
      (node (ref "S2") (pin "4") (pinfunction "4_4") (pintype "passive"))
    )
    (net (code "81") (name "unconnected-(S3-Pad2)") (class "Default")
      (node (ref "S3") (pin "2") (pinfunction "2_2") (pintype "passive"))
    )
    (net (code "82") (name "unconnected-(S3-Pad3)") (class "Default")
      (node (ref "S3") (pin "3") (pinfunction "3_3") (pintype "passive"))
    )
    (net (code "83") (name "unconnected-(U1-NC-Pad9)") (class "Default")
      (node (ref "U1") (pin "9") (pinfunction "NC_9") (pintype "bidirectional"))
    )
    (net (code "84") (name "unconnected-(U1-NC-Pad44)") (class "Default")
      (node (ref "U1") (pin "44") (pinfunction "NC_44") (pintype "bidirectional"))
    )
    (net (code "85") (name "unconnected-(U1-RTC_BTN-Pad74)") (class "Default")
      (node (ref "U1") (pin "74") (pinfunction "RTC_BTN_74") (pintype "bidirectional"))
    )
  )
)
